# ps2_connector.net
KiCad netlist of a schematic drawn in Altium Designer
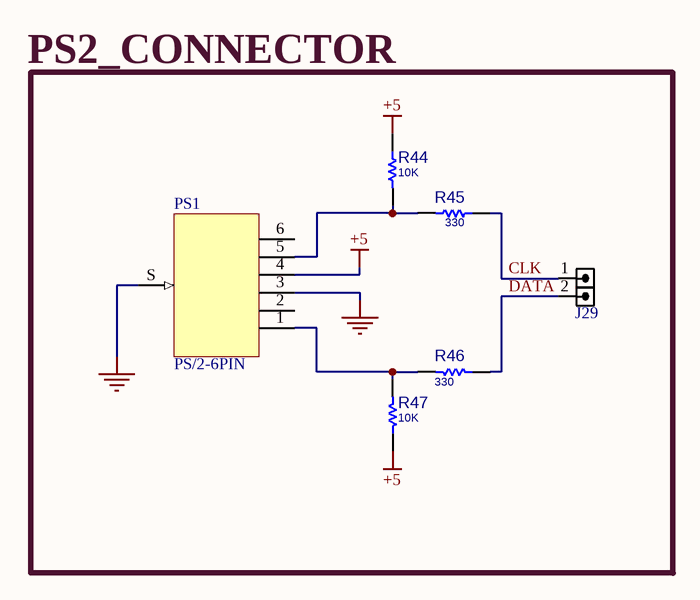
[diagram p0: ps2_connector.SchDoc]

(export (version "E")
  (design (tool "Eeschema 10.0.6"))
  (components
    (comp (ref "J29")
      (value "HDRMINI_2")
      (footprint "HDRMINI_M_1X2")
      (description "CONN, HEADER, Male, pitch: 1.27mm, 2POS")
      (libsource (lib "AvrDevelopmentBoard") (part "HDRMINI_M_1X2_1"))
    )
    (comp (ref "PS1")
      (value "PS/2-6PIN")
      (description "CREATED BY J")
      (libsource (lib "AvrDevelopmentBoard") (part "PS/2_CONNECTOR"))
    )
    (comp (ref "R44")
      (value "10K")
      (footprint "R025W_AX04")
      (description "RESISTOR, THD")
      (fields (field (name "MANF_P#") "RK73H1ETTP4701F") (field (name "MANF") "KOA SPEER"))
      (libsource (lib "passive_thd") (part "RES_THD"))
    )
    (comp (ref "R45")
      (value "330")
      (footprint "R025W_AX04")
      (description "RESISTOR, THD")
      (fields (field (name "MANF_P#") "RK73H1ETTP4701F") (field (name "MANF") "KOA SPEER"))
      (libsource (lib "passive_thd") (part "RES_THD"))
    )
    (comp (ref "R46")
      (value "330")
      (footprint "R025W_AX04")
      (description "RESISTOR, THD")
      (fields (field (name "MANF_P#") "RK73H1ETTP4701F") (field (name "MANF") "KOA SPEER"))
      (libsource (lib "passive_thd") (part "RES_THD"))
    )
    (comp (ref "R47")
      (value "10K")
      (footprint "R025W_AX04")
      (description "RESISTOR, THD")
      (fields (field (name "MANF_P#") "RK73H1ETTP4701F") (field (name "MANF") "KOA SPEER"))
      (libsource (lib "passive_thd") (part "RES_THD"))
    )
  )
  (nets
    (net (code "1") (name "+5") (class "Default")
      (node (ref "PS1") (pin "4") (pinfunction "4_4") (pintype "passive"))
      (node (ref "R44") (pin "1") (pinfunction "1_1") (pintype "passive"))
      (node (ref "R47") (pin "1") (pinfunction "1_1") (pintype "passive"))
    )
    (net (code "2") (name "/CLK") (class "Default")
      (node (ref "J29") (pin "1") (pinfunction "1_1") (pintype "passive"))
      (node (ref "R45") (pin "1") (pinfunction "1_1") (pintype "passive"))
    )
    (net (code "3") (name "/DATA") (class "Default")
      (node (ref "J29") (pin "2") (pinfunction "2_2") (pintype "passive"))
      (node (ref "R46") (pin "1") (pinfunction "1_1") (pintype "passive"))
    )
    (net (code "4") (name "GND") (class "Default")
      (node (ref "PS1") (pin "3") (pinfunction "3_3") (pintype "passive"))
      (node (ref "PS1") (pin "S") (pinfunction "7_S") (pintype "input"))
    )
    (net (code "5") (name "Net-(PS1-Pad1)") (class "Default")
      (node (ref "PS1") (pin "1") (pinfunction "1_1") (pintype "passive"))
      (node (ref "R46") (pin "2") (pinfunction "2_2") (pintype "passive"))
      (node (ref "R47") (pin "2") (pinfunction "2_2") (pintype "passive"))
    )
    (net (code "6") (name "Net-(PS1-Pad5)") (class "Default")
      (node (ref "PS1") (pin "5") (pinfunction "5_5") (pintype "passive"))
      (node (ref "R44") (pin "2") (pinfunction "2_2") (pintype "passive"))
      (node (ref "R45") (pin "2") (pinfunction "2_2") (pintype "passive"))
    )
    (net (code "7") (name "unconnected-(PS1-Pad2)") (class "Default")
      (node (ref "PS1") (pin "2") (pinfunction "2_2") (pintype "passive"))
    )
    (net (code "8") (name "unconnected-(PS1-Pad6)") (class "Default")
      (node (ref "PS1") (pin "6") (pinfunction "6_6") (pintype "passive"))
    )
  )
)
